# Photo-Diode_Board.net
KiCad netlist of a schematic drawn in Altium Designer
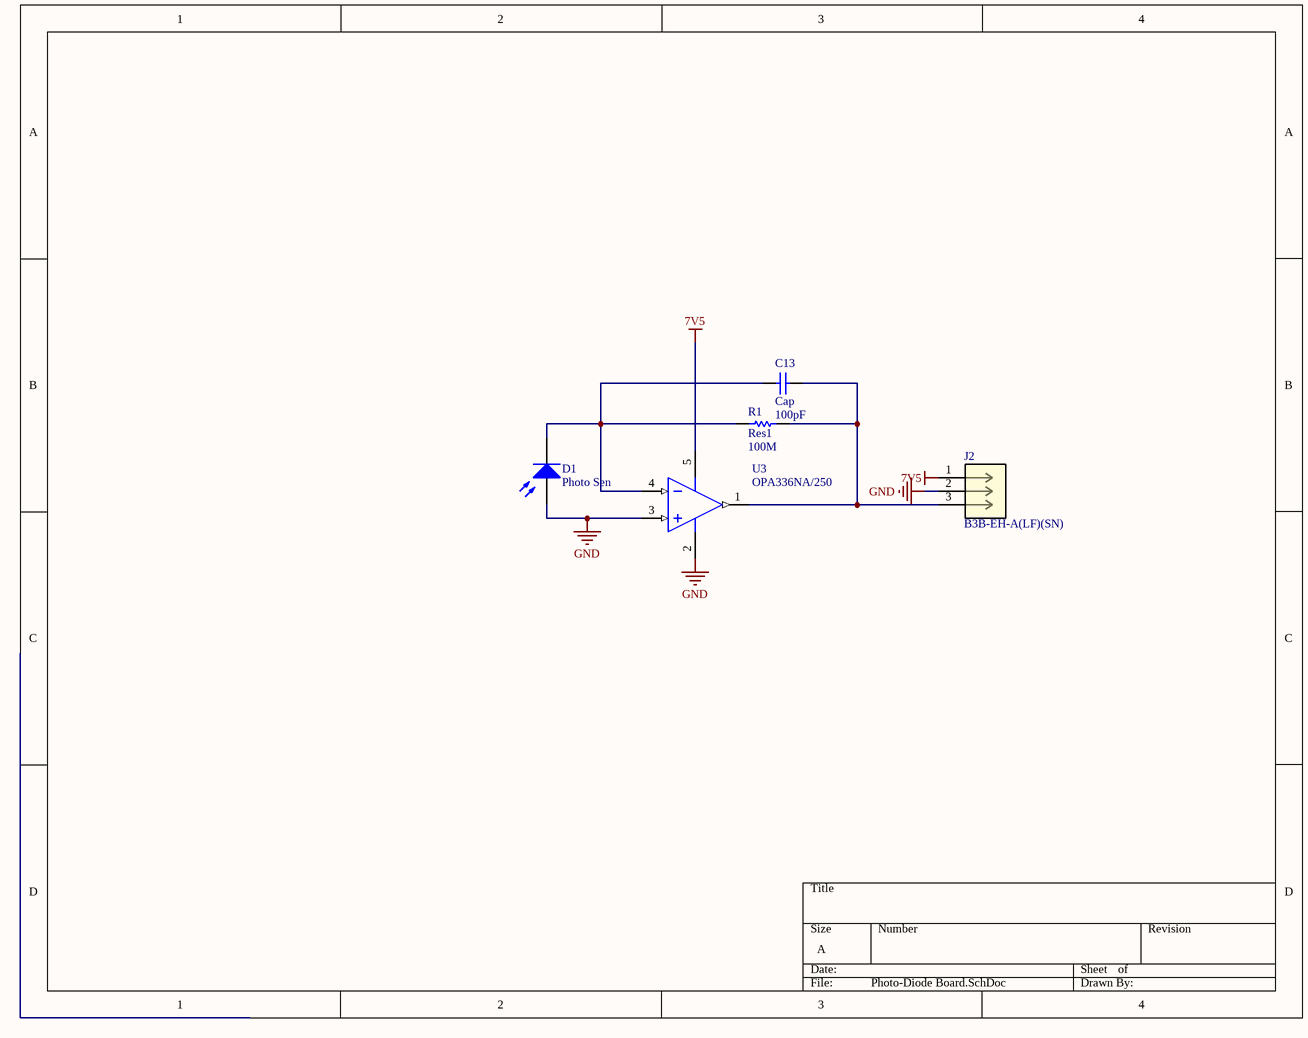
[diagram p0: Photo-Diode Board.SchDoc]

(export (version "E")
  (design (tool "Eeschema 10.0.6"))
  (components
    (comp (ref "C13")
      (value "Cap")
      (footprint "0402-A")
      (description "Capacitor")
      (fields (field (name "ALTIUM_VALUE") "100pF") (field (name "PUBLISHER") "Altium Limited"))
      (libsource (lib "Miscellaneous Devices") (part "Cap"))
    )
    (comp (ref "D1")
      (value "Photo Sen")
      (footprint "PIN2")
      (description "Photosensitive Diode")
      (fields (field (name "PUBLISHER") "Altium Limited"))
      (libsource (lib "Miscellaneous Devices") (part "Photo Sen"))
    )
    (comp (ref "J2")
      (value "B3B-EH-A(LF)(SN)")
      (footprint "CONN3_B3B-EH-A(LF)(SN)_JST")
      (description "No Description Available")
      (fields (field (name "COPYRIGHT") "Copyright (C) 2018 Accelerated Designs. All rights reserved"))
      (libsource (lib "2020-10-15_19-17-05") (part "B3B-EH-A(LF)(SN)"))
    )
    (comp (ref "R1")
      (value "Res1")
      (footprint "1608[0603]")
      (description "Resistor")
      (fields (field (name "ALTIUM_VALUE") "100M") (field (name "PUBLISHER") "Altium Limited"))
      (libsource (lib "Miscellaneous Devices") (part "Res1"))
    )
    (comp (ref "U3")
      (value "OPA336NA/250")
      (footprint "DBV0005A_M")
      (fields (field (name "MANUFACTURER") "Texas Instruments"))
      (libsource (lib "Altium Content Vault") (part "TI-OPA_SM7XXXX-DBV5"))
    )
  )
  (nets
    (net (code "1") (name "7V5") (class "Default")
      (node (ref "J2") (pin "1") (pinfunction "1_1") (pintype "passive"))
      (node (ref "U3") (pin "5") (pinfunction "V+_5") (pintype "power_in"))
    )
    (net (code "2") (name "GND") (class "Default")
      (node (ref "D1") (pin "1") (pinfunction "A_1") (pintype "passive"))
      (node (ref "J2") (pin "2") (pinfunction "2_2") (pintype "passive"))
      (node (ref "U3") (pin "2") (pinfunction "V-_2") (pintype "power_in"))
      (node (ref "U3") (pin "3") (pinfunction "IN+_3") (pintype "input"))
    )
    (net (code "3") (name "Net-(D1-K)") (class "Default")
      (node (ref "C13") (pin "1") (pinfunction "1_1") (pintype "passive"))
      (node (ref "D1") (pin "2") (pinfunction "K_2") (pintype "passive"))
      (node (ref "R1") (pin "1") (pinfunction "1_1") (pintype "passive"))
      (node (ref "U3") (pin "4") (pinfunction "IN-_4") (pintype "input"))
    )
    (net (code "4") (name "Net-(U3-OUT)") (class "Default")
      (node (ref "C13") (pin "2") (pinfunction "2_2") (pintype "passive"))
      (node (ref "J2") (pin "3") (pinfunction "3_3") (pintype "passive"))
      (node (ref "R1") (pin "2") (pinfunction "2_2") (pintype "passive"))
      (node (ref "U3") (pin "1") (pinfunction "OUT_1") (pintype "output"))
    )
  )
)
